# STM_Schematic.net
KiCad netlist of a schematic drawn in Altium Designer
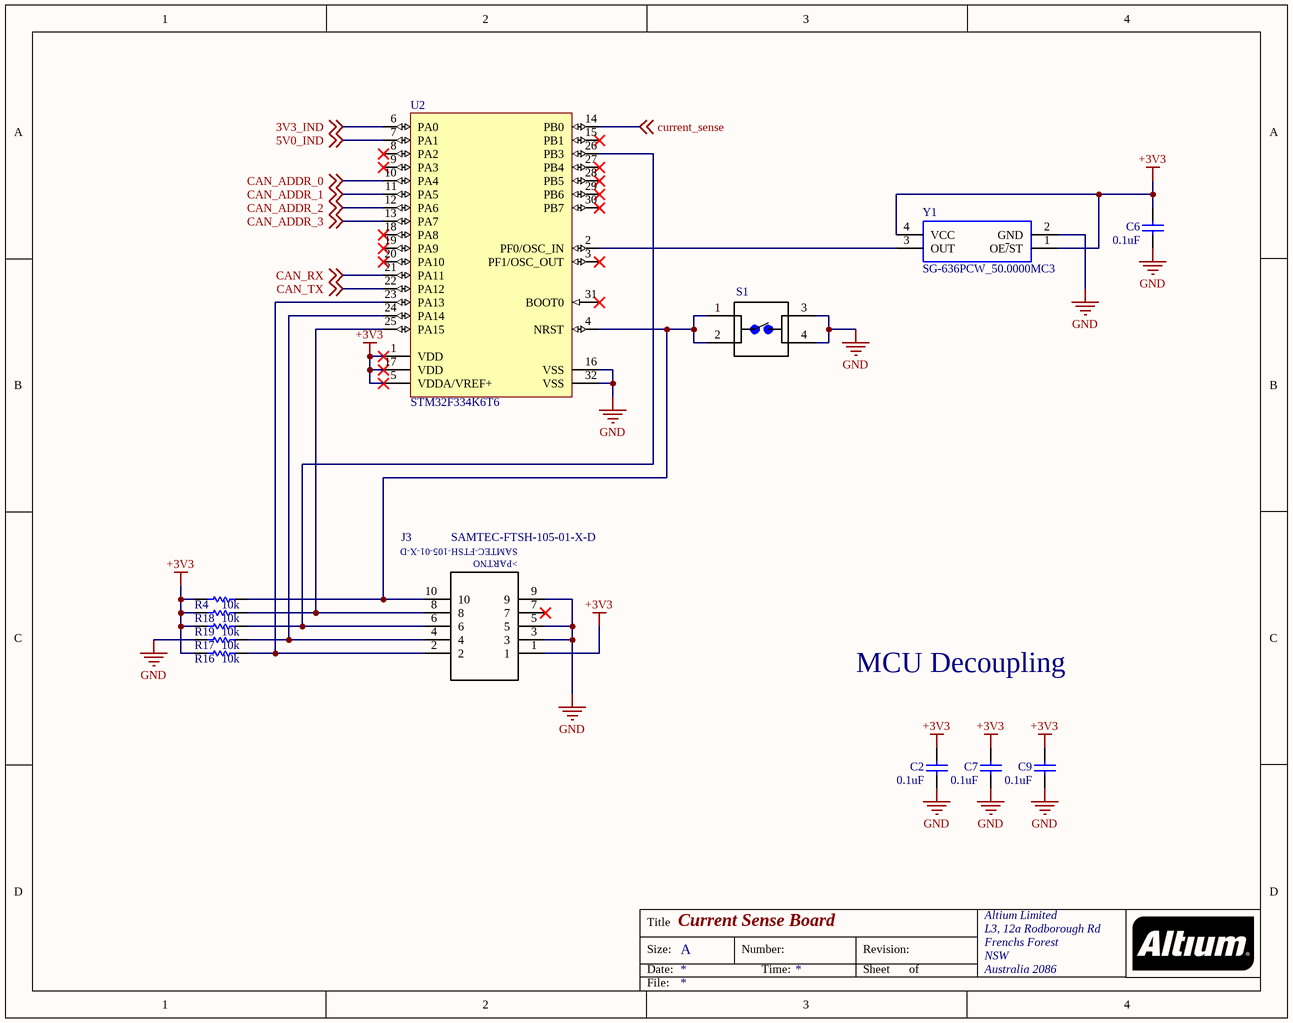
[diagram p0: STM Schematic.SchDoc]

(export (version "E")
  (design (tool "Eeschema 10.0.6"))
  (components
    (comp (ref "C2")
      (value "0.1uF")
      (footprint "CAPC0805(2012)75_L")
      (description "CAP 2.7pF 50V ±0.1pF 0805 (2012 Metric) Thickness 0.75mm SMD")
      (fields (field (name "TOLERANCE") "Â±0.1pF"))
      (libsource (lib "Integrated_Library - 12.01.19 - 13.05") (part "CMP-1036-00339-1"))
    )
    (comp (ref "C6")
      (value "0.1uF")
      (footprint "CAPC0805(2012)75_L")
      (description "CAP 2.7pF 50V ±0.1pF 0805 (2012 Metric) Thickness 0.75mm SMD")
      (fields (field (name "TOLERANCE") "Â±0.1pF"))
      (libsource (lib "Integrated_Library - 12.01.19 - 13.05") (part "CMP-1036-00339-1"))
    )
    (comp (ref "C7")
      (value "0.1uF")
      (footprint "CAPC0805(2012)75_L")
      (description "CAP 2.7pF 50V ±0.1pF 0805 (2012 Metric) Thickness 0.75mm SMD")
      (fields (field (name "TOLERANCE") "Â±0.1pF"))
      (libsource (lib "Integrated_Library - 12.01.19 - 13.05") (part "CMP-1036-00339-1"))
    )
    (comp (ref "C9")
      (value "0.1uF")
      (footprint "CAPC0805(2012)75_L")
      (description "CAP 2.7pF 50V ±0.1pF 0805 (2012 Metric) Thickness 0.75mm SMD")
      (fields (field (name "TOLERANCE") "Â±0.1pF"))
      (libsource (lib "Integrated_Library - 12.01.19 - 13.05") (part "CMP-1036-00339-1"))
    )
    (comp (ref "J3")
      (value "SAMTEC-FTSH-105-01-X-D")
      (footprint "SAMTEC-FTSH-105-01-X-D")
      (libsource (lib "Husky Robotics Standard Library 2019-2020") (part "SAMTEC-FTSH-105-01-X-D"))
    )
    (comp (ref "R4")
      (value "10k")
      (footprint "RESC2013X70X40LL20T20")
      (description "RES SMD 150K OHM 1% 1/8W 0805")
      (fields (field (name "MANUFACTURER") "Panasonic") (field (name "PART NUMBER") "ERJ-6ENF1503V"))
      (libsource (lib "Altium Content Vault") (part "RES"))
    )
    (comp (ref "R16")
      (value "10k")
      (footprint "RESC2013X70X40LL20T20")
      (description "RES SMD 150K OHM 1% 1/8W 0805")
      (fields (field (name "MANUFACTURER") "Panasonic") (field (name "PART NUMBER") "ERJ-6ENF1503V"))
      (libsource (lib "Altium Content Vault") (part "RES"))
    )
    (comp (ref "R17")
      (value "10k")
      (footprint "RESC2013X70X40LL20T20")
      (description "RES SMD 150K OHM 1% 1/8W 0805")
      (fields (field (name "MANUFACTURER") "Panasonic") (field (name "PART NUMBER") "ERJ-6ENF1503V"))
      (libsource (lib "Altium Content Vault") (part "RES"))
    )
    (comp (ref "R18")
      (value "10k")
      (footprint "RESC2013X70X40LL20T20")
      (description "RES SMD 150K OHM 1% 1/8W 0805")
      (fields (field (name "MANUFACTURER") "Panasonic") (field (name "PART NUMBER") "ERJ-6ENF1503V"))
      (libsource (lib "Altium Content Vault") (part "RES"))
    )
    (comp (ref "R19")
      (value "10k")
      (footprint "RESC2013X70X40LL20T20")
      (description "RES SMD 150K OHM 1% 1/8W 0805")
      (fields (field (name "MANUFACTURER") "Panasonic") (field (name "PART NUMBER") "ERJ-6ENF1503V"))
      (libsource (lib "Altium Content Vault") (part "RES"))
    )
    (comp (ref "S1")
      (value "1825910-7")
      (footprint "Switch 6mm 24V (NO)")
      (description "FSM4JAH=6MM TACT SWITCH, HIGH TEMP")
      (fields (field (name "MF") "TE Connectivity") (field (name "DIGI-KEY_PART_NUMBER") "450-1804-ND"))
      (libsource (lib "Husky Robotics Standard Library 2019-2020") (part "Switch 6mm 24V (NO)"))
    )
    (comp (ref "U2")
      (value "STM32F334K6T6")
      (footprint "STM-LQFP32_N")
      (libsource (lib "Husky Robotics Standard Library 2019-2020") (part "STM32F334K6T6"))
    )
    (comp (ref "Y1")
      (value "SG-636PCW_50.0000MC3")
      (footprint "SG-636")
      (description "Standard Clock Oscillators 50MHz 3.3Volt 100ppm -20C +70C")
      (fields (field (name "MANUFACTURER_PART_NUMBER") "SG-636PCW 50.0000MC3: ROHS"))
      (libsource (lib "SG-636 PTF_50") (part "SG-636PCW_50.0000MC3__ROHS"))
    )
  )
  (nets
    (net (code "1") (name "+3V3") (class "Default")
      (node (ref "C2") (pin "2") (pinfunction "2_2") (pintype "passive"))
      (node (ref "C6") (pin "2") (pinfunction "2_2") (pintype "passive"))
      (node (ref "C7") (pin "2") (pinfunction "2_2") (pintype "passive"))
      (node (ref "C9") (pin "2") (pinfunction "2_2") (pintype "passive"))
      (node (ref "J3") (pin "1") (pinfunction "1_1") (pintype "passive"))
      (node (ref "R16") (pin "1") (pinfunction "1_1") (pintype "passive"))
      (node (ref "R18") (pin "1") (pinfunction "1_1") (pintype "passive"))
      (node (ref "R19") (pin "1") (pinfunction "1_1") (pintype "passive"))
      (node (ref "R4") (pin "1") (pinfunction "1_1") (pintype "passive"))
      (node (ref "U2") (pin "1") (pinfunction "VDD_1") (pintype "power_in"))
      (node (ref "U2") (pin "17") (pinfunction "VDD_17") (pintype "power_in"))
      (node (ref "U2") (pin "5") (pinfunction "VDDA/VREF+_5") (pintype "power_in"))
      (node (ref "Y1") (pin "1") (pinfunction "OE~{/}ST_1") (pintype "passive"))
      (node (ref "Y1") (pin "4") (pinfunction "VCC_4") (pintype "power_in"))
    )
    (net (code "2") (name "3V3_IND") (class "Default")
      (node (ref "U2") (pin "6") (pinfunction "PA0_6") (pintype "bidirectional"))
    )
    (net (code "3") (name "5V0_IND") (class "Default")
      (node (ref "U2") (pin "7") (pinfunction "PA1_7") (pintype "bidirectional"))
    )
    (net (code "4") (name "CAN_ADDR_0") (class "Default")
      (node (ref "U2") (pin "10") (pinfunction "PA4_10") (pintype "bidirectional"))
    )
    (net (code "5") (name "CAN_ADDR_1") (class "Default")
      (node (ref "U2") (pin "11") (pinfunction "PA5_11") (pintype "bidirectional"))
    )
    (net (code "6") (name "CAN_ADDR_2") (class "Default")
      (node (ref "U2") (pin "12") (pinfunction "PA6_12") (pintype "bidirectional"))
    )
    (net (code "7") (name "CAN_ADDR_3") (class "Default")
      (node (ref "U2") (pin "13") (pinfunction "PA7_13") (pintype "bidirectional"))
    )
    (net (code "8") (name "CAN_RX") (class "Default")
      (node (ref "U2") (pin "21") (pinfunction "PA11_21") (pintype "bidirectional"))
    )
    (net (code "9") (name "CAN_TX") (class "Default")
      (node (ref "U2") (pin "22") (pinfunction "PA12_22") (pintype "bidirectional"))
    )
    (net (code "10") (name "GND") (class "Default")
      (node (ref "C2") (pin "1") (pinfunction "1_1") (pintype "passive"))
      (node (ref "C6") (pin "1") (pinfunction "1_1") (pintype "passive"))
      (node (ref "C7") (pin "1") (pinfunction "1_1") (pintype "passive"))
      (node (ref "C9") (pin "1") (pinfunction "1_1") (pintype "passive"))
      (node (ref "J3") (pin "3") (pinfunction "3_3") (pintype "passive"))
      (node (ref "J3") (pin "5") (pinfunction "5_5") (pintype "passive"))
      (node (ref "J3") (pin "9") (pinfunction "9_9") (pintype "passive"))
      (node (ref "R17") (pin "1") (pinfunction "1_1") (pintype "passive"))
      (node (ref "S1") (pin "3") (pinfunction "3_3") (pintype "passive"))
      (node (ref "S1") (pin "4") (pinfunction "4_4") (pintype "passive"))
      (node (ref "U2") (pin "16") (pinfunction "VSS_16") (pintype "power_in"))
      (node (ref "U2") (pin "32") (pinfunction "VSS_32") (pintype "power_in"))
      (node (ref "Y1") (pin "2") (pinfunction "GND_2") (pintype "passive"))
    )
    (net (code "11") (name "Net-(U2-NRST)") (class "Default")
      (node (ref "J3") (pin "10") (pinfunction "10_10") (pintype "passive"))
      (node (ref "R4") (pin "2") (pinfunction "2_2") (pintype "passive"))
      (node (ref "S1") (pin "1") (pinfunction "1_1") (pintype "passive"))
      (node (ref "S1") (pin "2") (pinfunction "2_2") (pintype "passive"))
      (node (ref "U2") (pin "4") (pinfunction "NRST_4") (pintype "bidirectional"))
    )
    (net (code "12") (name "Net-(U2-PA13)") (class "Default")
      (node (ref "J3") (pin "2") (pinfunction "2_2") (pintype "passive"))
      (node (ref "R16") (pin "2") (pinfunction "2_2") (pintype "passive"))
      (node (ref "U2") (pin "23") (pinfunction "PA13_23") (pintype "bidirectional"))
    )
    (net (code "13") (name "Net-(U2-PA14)") (class "Default")
      (node (ref "J3") (pin "4") (pinfunction "4_4") (pintype "passive"))
      (node (ref "R17") (pin "2") (pinfunction "2_2") (pintype "passive"))
      (node (ref "U2") (pin "24") (pinfunction "PA14_24") (pintype "bidirectional"))
    )
    (net (code "14") (name "Net-(U2-PA15)") (class "Default")
      (node (ref "J3") (pin "8") (pinfunction "8_8") (pintype "passive"))
      (node (ref "R18") (pin "2") (pinfunction "2_2") (pintype "passive"))
      (node (ref "U2") (pin "25") (pinfunction "PA15_25") (pintype "bidirectional"))
    )
    (net (code "15") (name "Net-(U2-PB3)") (class "Default")
      (node (ref "J3") (pin "6") (pinfunction "6_6") (pintype "passive"))
      (node (ref "R19") (pin "2") (pinfunction "2_2") (pintype "passive"))
      (node (ref "U2") (pin "26") (pinfunction "PB3_26") (pintype "bidirectional"))
    )
    (net (code "16") (name "Net-(U2-PF0{slash}OSC_IN)") (class "Default")
      (node (ref "U2") (pin "2") (pinfunction "PF0/OSC_IN_2") (pintype "bidirectional"))
      (node (ref "Y1") (pin "3") (pinfunction "OUT_3") (pintype "passive"))
    )
    (net (code "17") (name "current_sense") (class "Default")
      (node (ref "U2") (pin "14") (pinfunction "PB0_14") (pintype "bidirectional"))
    )
    (net (code "18") (name "unconnected-(J3-Pad7)") (class "Default")
      (node (ref "J3") (pin "7") (pinfunction "7_7") (pintype "passive+no_connect"))
    )
    (net (code "19") (name "unconnected-(U2-BOOT0-Pad31)") (class "Default")
      (node (ref "U2") (pin "31") (pinfunction "BOOT0_31") (pintype "input+no_connect"))
    )
    (net (code "20") (name "unconnected-(U2-PA2-Pad8)") (class "Default")
      (node (ref "U2") (pin "8") (pinfunction "PA2_8") (pintype "bidirectional+no_connect"))
    )
    (net (code "21") (name "unconnected-(U2-PA3-Pad9)") (class "Default")
      (node (ref "U2") (pin "9") (pinfunction "PA3_9") (pintype "bidirectional+no_connect"))
    )
    (net (code "22") (name "unconnected-(U2-PA8-Pad18)") (class "Default")
      (node (ref "U2") (pin "18") (pinfunction "PA8_18") (pintype "bidirectional+no_connect"))
    )
    (net (code "23") (name "unconnected-(U2-PA9-Pad19)") (class "Default")
      (node (ref "U2") (pin "19") (pinfunction "PA9_19") (pintype "bidirectional+no_connect"))
    )
    (net (code "24") (name "unconnected-(U2-PA10-Pad20)") (class "Default")
      (node (ref "U2") (pin "20") (pinfunction "PA10_20") (pintype "bidirectional+no_connect"))
    )
    (net (code "25") (name "unconnected-(U2-PB1-Pad15)") (class "Default")
      (node (ref "U2") (pin "15") (pinfunction "PB1_15") (pintype "bidirectional+no_connect"))
    )
    (net (code "26") (name "unconnected-(U2-PB4-Pad27)") (class "Default")
      (node (ref "U2") (pin "27") (pinfunction "PB4_27") (pintype "bidirectional+no_connect"))
    )
    (net (code "27") (name "unconnected-(U2-PB5-Pad28)") (class "Default")
      (node (ref "U2") (pin "28") (pinfunction "PB5_28") (pintype "bidirectional+no_connect"))
    )
    (net (code "28") (name "unconnected-(U2-PB6-Pad29)") (class "Default")
      (node (ref "U2") (pin "29") (pinfunction "PB6_29") (pintype "bidirectional+no_connect"))
    )
    (net (code "29") (name "unconnected-(U2-PB7-Pad30)") (class "Default")
      (node (ref "U2") (pin "30") (pinfunction "PB7_30") (pintype "bidirectional+no_connect"))
    )
    (net (code "30") (name "unconnected-(U2-PF1{slash}OSC_OUT-Pad3)") (class "Default")
      (node (ref "U2") (pin "3") (pinfunction "PF1/OSC_OUT_3") (pintype "bidirectional+no_connect"))
    )
  )
)
